# M5921A.net
KiCad netlist of a schematic drawn in EAGLE
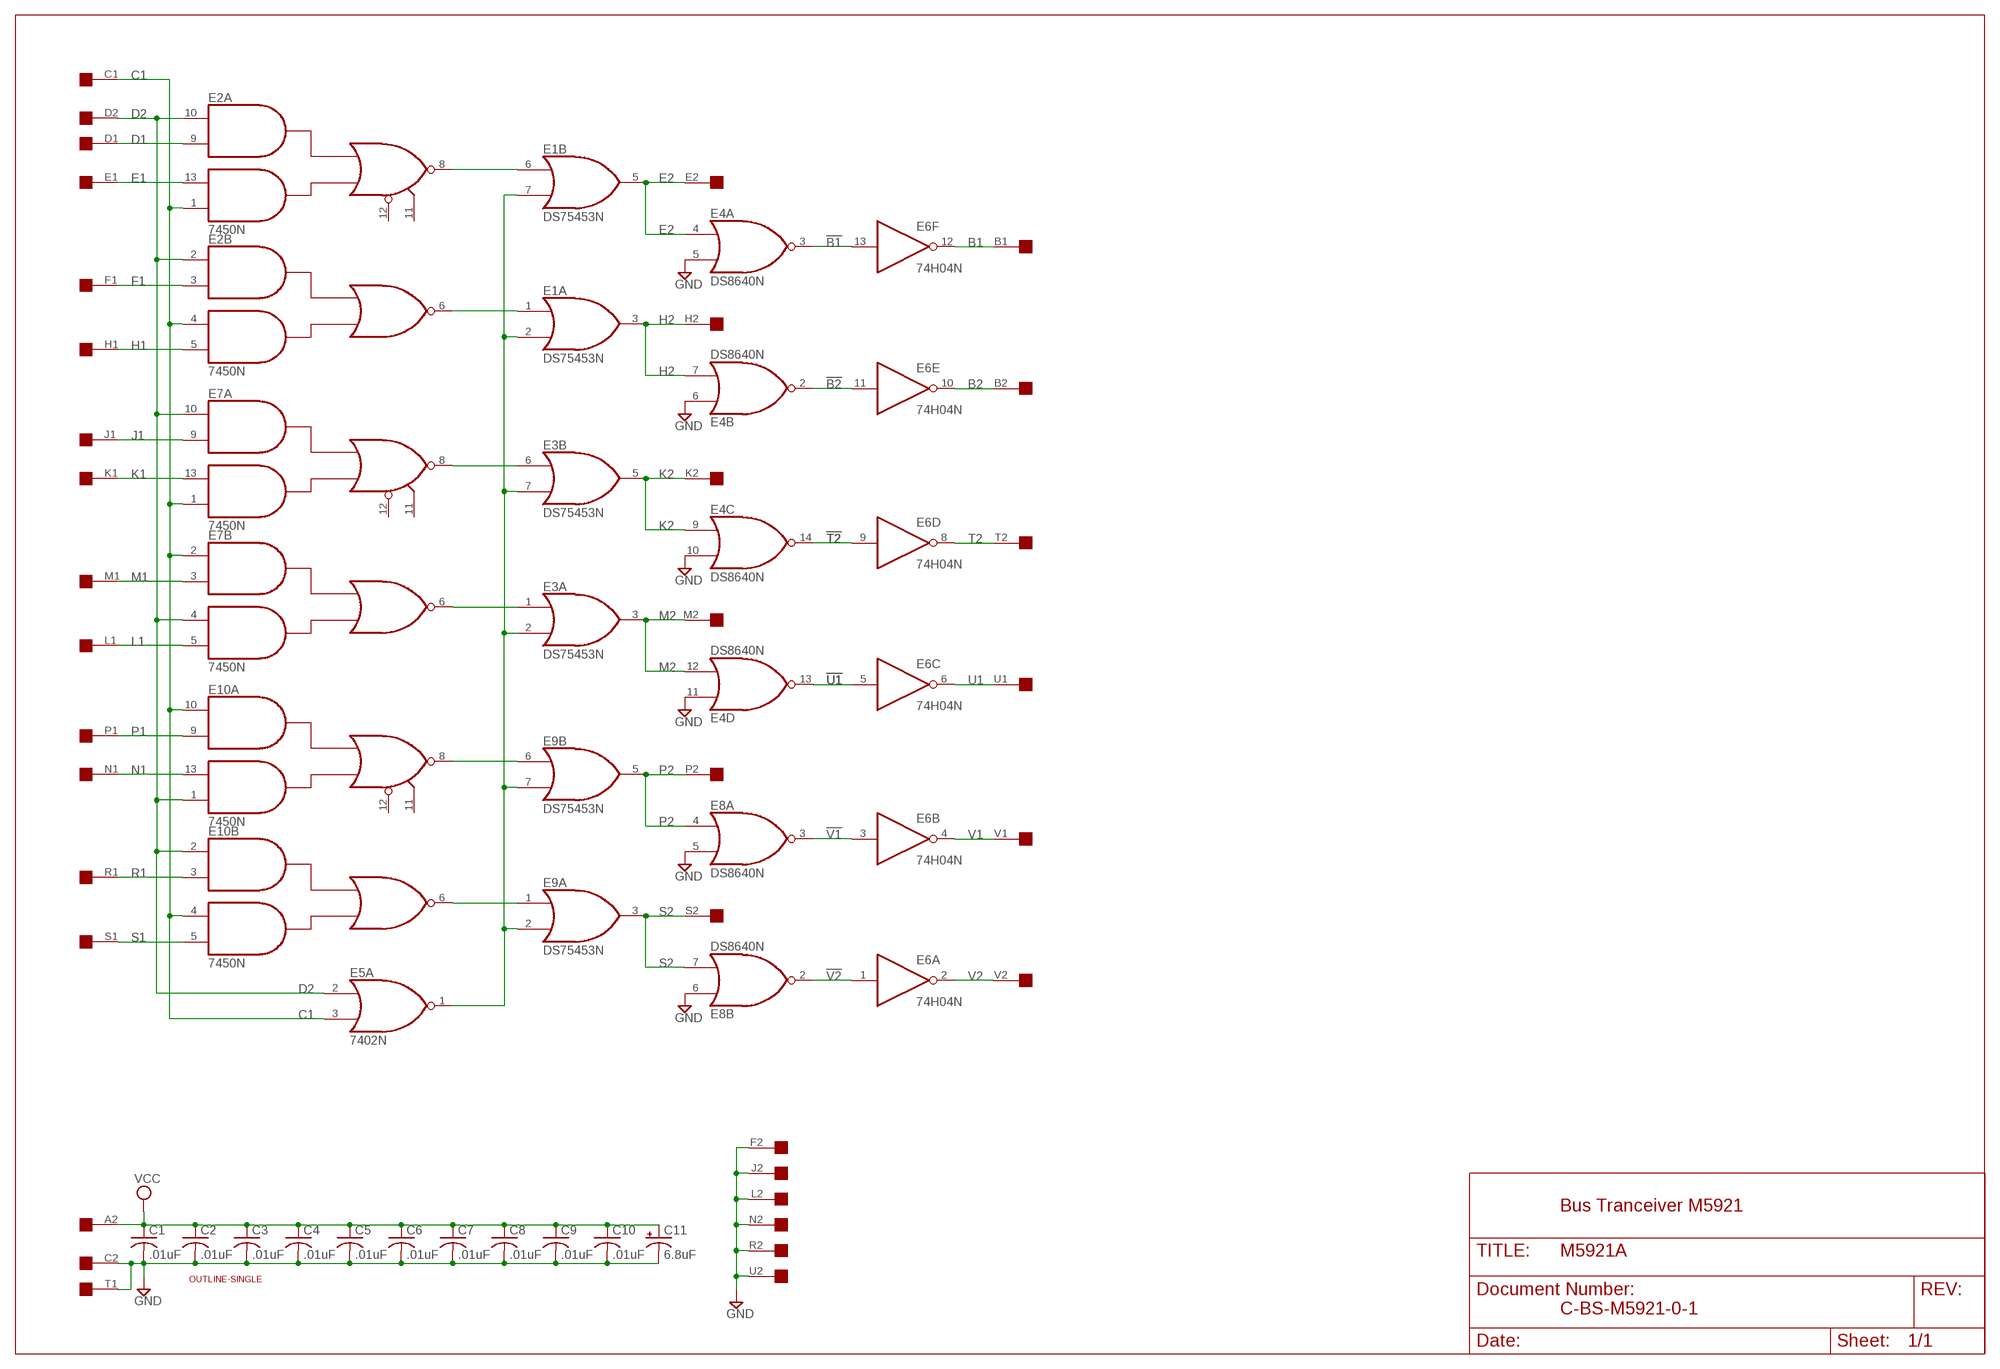
[diagram p0: schematic, sheet 1]

(export (version "E")
  (design (tool "Eeschema 10.0.6"))
  (components
    (comp (ref "C1")
      (value ".01uF")
      (footprint "eagle-import:C063-025X075")
      (libsource (lib "eagle-import") (part "C-US"))
    )
    (comp (ref "C2")
      (value ".01uF")
      (footprint "eagle-import:C063-025X075")
      (libsource (lib "eagle-import") (part "C-US"))
    )
    (comp (ref "C3")
      (value ".01uF")
      (footprint "eagle-import:C063-025X075")
      (libsource (lib "eagle-import") (part "C-US"))
    )
    (comp (ref "C4")
      (value ".01uF")
      (footprint "eagle-import:C063-025X075")
      (libsource (lib "eagle-import") (part "C-US"))
    )
    (comp (ref "C5")
      (value ".01uF")
      (footprint "eagle-import:C063-025X075")
      (libsource (lib "eagle-import") (part "C-US"))
    )
    (comp (ref "C6")
      (value ".01uF")
      (footprint "eagle-import:C063-025X075")
      (libsource (lib "eagle-import") (part "C-US"))
    )
    (comp (ref "C7")
      (value ".01uF")
      (footprint "eagle-import:C063-025X075")
      (libsource (lib "eagle-import") (part "C-US"))
    )
    (comp (ref "C8")
      (value ".01uF")
      (footprint "eagle-import:C063-025X075")
      (libsource (lib "eagle-import") (part "C-US"))
    )
    (comp (ref "C9")
      (value ".01uF")
      (footprint "eagle-import:C063-025X075")
      (libsource (lib "eagle-import") (part "C-US"))
    )
    (comp (ref "C10")
      (value ".01uF")
      (footprint "eagle-import:C063-025X075")
      (libsource (lib "eagle-import") (part "C-US"))
    )
    (comp (ref "C11")
      (value "6.8uF")
      (footprint "eagle-import:E15-5")
      (libsource (lib "eagle-import") (part "CPOL-USE15-5AXIAL"))
    )
    (comp (ref "E1")
      (value "DS75453N")
      (footprint "eagle-import:DIL08")
      (libsource (lib "eagle-import") (part "DS75453N"))
    )
    (comp (ref "E2")
      (value "7450N")
      (footprint "eagle-import:DIL14")
      (libsource (lib "eagle-import") (part "7450N"))
    )
    (comp (ref "E3")
      (value "DS75453N")
      (footprint "eagle-import:DIL08")
      (libsource (lib "eagle-import") (part "DS75453N"))
    )
    (comp (ref "E4")
      (value "DS8640N")
      (footprint "eagle-import:DIL14")
      (libsource (lib "eagle-import") (part "DS8640N"))
    )
    (comp (ref "E5")
      (value "7402N")
      (footprint "eagle-import:DIL14")
      (libsource (lib "eagle-import") (part "7402N"))
    )
    (comp (ref "E6")
      (value "74H04N")
      (footprint "eagle-import:DIL14")
      (libsource (lib "eagle-import") (part "7404NS"))
    )
    (comp (ref "E7")
      (value "7450N")
      (footprint "eagle-import:DIL14")
      (libsource (lib "eagle-import") (part "7450N"))
    )
    (comp (ref "E8")
      (value "DS8640N")
      (footprint "eagle-import:DIL14")
      (libsource (lib "eagle-import") (part "DS8640N"))
    )
    (comp (ref "E9")
      (value "DS75453N")
      (footprint "eagle-import:DIL08")
      (libsource (lib "eagle-import") (part "DS75453N"))
    )
    (comp (ref "E10")
      (value "7450N")
      (footprint "eagle-import:DIL14")
      (libsource (lib "eagle-import") (part "7450N"))
    )
    (comp (ref "U$1")
      (value "OUTLINE-SINGLE")
      (footprint "eagle-import:SINGLE")
      (libsource (lib "eagle-import") (part "OUTLINE-SINGLE"))
    )
    (comp (ref "U$2")
      (value "edge")
      (footprint "eagle-import:EDGE-CON2")
      (libsource (lib "eagle-import") (part "SINGLE"))
    )
  )
  (nets
    (net (code "1") (name "/B1") (class "Default")
      (node (ref "E6") (pin "12") (pinfunction "O_12") (pintype "output"))
      (node (ref "U$2") (pin "B1") (pinfunction "1_B1") (pintype "bidirectional"))
    )
    (net (code "2") (name "/B2") (class "Default")
      (node (ref "E6") (pin "10") (pinfunction "O_10") (pintype "output"))
      (node (ref "U$2") (pin "B2") (pinfunction "1_B2") (pintype "bidirectional"))
    )
    (net (code "3") (name "/C1") (class "Default")
      (node (ref "E10") (pin "10") (pinfunction "I1_10") (pintype "input"))
      (node (ref "E10") (pin "4") (pinfunction "I3_4") (pintype "input"))
      (node (ref "E2") (pin "1") (pinfunction "I4_1") (pintype "input"))
      (node (ref "E2") (pin "4") (pinfunction "I3_4") (pintype "input"))
      (node (ref "E5") (pin "3") (pinfunction "I1_3") (pintype "input"))
      (node (ref "E7") (pin "1") (pinfunction "I4_1") (pintype "input"))
      (node (ref "E7") (pin "2") (pinfunction "I1_2") (pintype "input"))
      (node (ref "U$2") (pin "C1") (pinfunction "1_C1") (pintype "bidirectional"))
    )
    (net (code "4") (name "/D1") (class "Default")
      (node (ref "E2") (pin "9") (pinfunction "I2_9") (pintype "input"))
      (node (ref "U$2") (pin "D1") (pinfunction "1_D1") (pintype "bidirectional"))
    )
    (net (code "5") (name "/D2") (class "Default")
      (node (ref "E10") (pin "1") (pinfunction "I4_1") (pintype "input"))
      (node (ref "E10") (pin "2") (pinfunction "I1_2") (pintype "input"))
      (node (ref "E2") (pin "10") (pinfunction "I1_10") (pintype "input"))
      (node (ref "E2") (pin "2") (pinfunction "I1_2") (pintype "input"))
      (node (ref "E5") (pin "2") (pinfunction "I0_2") (pintype "input"))
      (node (ref "E7") (pin "10") (pinfunction "I1_10") (pintype "input"))
      (node (ref "E7") (pin "4") (pinfunction "I3_4") (pintype "input"))
      (node (ref "U$2") (pin "D2") (pinfunction "1_D2") (pintype "bidirectional"))
    )
    (net (code "6") (name "/E1") (class "Default")
      (node (ref "E2") (pin "13") (pinfunction "I3_13") (pintype "input"))
      (node (ref "U$2") (pin "E1") (pinfunction "1_E1") (pintype "bidirectional"))
    )
    (net (code "7") (name "/E2") (class "Default")
      (node (ref "E1") (pin "5") (pinfunction "O_5") (pintype "open_collector"))
      (node (ref "E4") (pin "4") (pinfunction "I0_4") (pintype "input"))
      (node (ref "U$2") (pin "E2") (pinfunction "1_E2") (pintype "bidirectional"))
    )
    (net (code "8") (name "/F1") (class "Default")
      (node (ref "E2") (pin "3") (pinfunction "I2_3") (pintype "input"))
      (node (ref "U$2") (pin "F1") (pinfunction "1_F1") (pintype "bidirectional"))
    )
    (net (code "9") (name "/H1") (class "Default")
      (node (ref "E2") (pin "5") (pinfunction "I4_5") (pintype "input"))
      (node (ref "U$2") (pin "H1") (pinfunction "1_H1") (pintype "bidirectional"))
    )
    (net (code "10") (name "/H2") (class "Default")
      (node (ref "E1") (pin "3") (pinfunction "O_3") (pintype "open_collector"))
      (node (ref "E4") (pin "7") (pinfunction "I1_7") (pintype "input"))
      (node (ref "U$2") (pin "H2") (pinfunction "1_H2") (pintype "bidirectional"))
    )
    (net (code "11") (name "/J1") (class "Default")
      (node (ref "E7") (pin "9") (pinfunction "I2_9") (pintype "input"))
      (node (ref "U$2") (pin "J1") (pinfunction "1_J1") (pintype "bidirectional"))
    )
    (net (code "12") (name "/K1") (class "Default")
      (node (ref "E7") (pin "13") (pinfunction "I3_13") (pintype "input"))
      (node (ref "U$2") (pin "K1") (pinfunction "1_K1") (pintype "bidirectional"))
    )
    (net (code "13") (name "/K2") (class "Default")
      (node (ref "E3") (pin "5") (pinfunction "O_5") (pintype "open_collector"))
      (node (ref "E4") (pin "9") (pinfunction "I0_9") (pintype "input"))
      (node (ref "U$2") (pin "K2") (pinfunction "1_K2") (pintype "bidirectional"))
    )
    (net (code "14") (name "/L1") (class "Default")
      (node (ref "E7") (pin "5") (pinfunction "I4_5") (pintype "input"))
      (node (ref "U$2") (pin "L1") (pinfunction "1_L1") (pintype "bidirectional"))
    )
    (net (code "15") (name "/M1") (class "Default")
      (node (ref "E7") (pin "3") (pinfunction "I2_3") (pintype "input"))
      (node (ref "U$2") (pin "M1") (pinfunction "1_M1") (pintype "bidirectional"))
    )
    (net (code "16") (name "/M2") (class "Default")
      (node (ref "E3") (pin "3") (pinfunction "O_3") (pintype "open_collector"))
      (node (ref "E4") (pin "12") (pinfunction "I1_12") (pintype "input"))
      (node (ref "U$2") (pin "M2") (pinfunction "1_M2") (pintype "bidirectional"))
    )
    (net (code "17") (name "/N1") (class "Default")
      (node (ref "E10") (pin "13") (pinfunction "I3_13") (pintype "input"))
      (node (ref "U$2") (pin "N1") (pinfunction "1_N1") (pintype "bidirectional"))
    )
    (net (code "18") (name "/P1") (class "Default")
      (node (ref "E10") (pin "9") (pinfunction "I2_9") (pintype "input"))
      (node (ref "U$2") (pin "P1") (pinfunction "1_P1") (pintype "bidirectional"))
    )
    (net (code "19") (name "/P2") (class "Default")
      (node (ref "E8") (pin "4") (pinfunction "I0_4") (pintype "input"))
      (node (ref "E9") (pin "5") (pinfunction "O_5") (pintype "open_collector"))
      (node (ref "U$2") (pin "P2") (pinfunction "1_P2") (pintype "bidirectional"))
    )
    (net (code "20") (name "/R1") (class "Default")
      (node (ref "E10") (pin "3") (pinfunction "I2_3") (pintype "input"))
      (node (ref "U$2") (pin "R1") (pinfunction "1_R1") (pintype "bidirectional"))
    )
    (net (code "21") (name "/S1") (class "Default")
      (node (ref "E10") (pin "5") (pinfunction "I4_5") (pintype "input"))
      (node (ref "U$2") (pin "S1") (pinfunction "1_S1") (pintype "bidirectional"))
    )
    (net (code "22") (name "/S2") (class "Default")
      (node (ref "E8") (pin "7") (pinfunction "I1_7") (pintype "input"))
      (node (ref "E9") (pin "3") (pinfunction "O_3") (pintype "open_collector"))
      (node (ref "U$2") (pin "S2") (pinfunction "1_S2") (pintype "bidirectional"))
    )
    (net (code "23") (name "/T2") (class "Default")
      (node (ref "E6") (pin "8") (pinfunction "O_8") (pintype "output"))
      (node (ref "U$2") (pin "T2") (pinfunction "1_T2") (pintype "bidirectional"))
    )
    (net (code "24") (name "/U1") (class "Default")
      (node (ref "E6") (pin "6") (pinfunction "O_6") (pintype "output"))
      (node (ref "U$2") (pin "U1") (pinfunction "1_U1") (pintype "bidirectional"))
    )
    (net (code "25") (name "/V1") (class "Default")
      (node (ref "E6") (pin "4") (pinfunction "O_4") (pintype "output"))
      (node (ref "U$2") (pin "V1") (pinfunction "1_V1") (pintype "bidirectional"))
    )
    (net (code "26") (name "/V2") (class "Default")
      (node (ref "E6") (pin "2") (pinfunction "O_2") (pintype "output"))
      (node (ref "U$2") (pin "V2") (pinfunction "1_V2") (pintype "bidirectional"))
    )
    (net (code "27") (name "/~{B1}") (class "Default")
      (node (ref "E4") (pin "3") (pinfunction "O_3") (pintype "output"))
      (node (ref "E6") (pin "13") (pinfunction "I_13") (pintype "input"))
    )
    (net (code "28") (name "/~{B2}") (class "Default")
      (node (ref "E4") (pin "2") (pinfunction "O_2") (pintype "output"))
      (node (ref "E6") (pin "11") (pinfunction "I_11") (pintype "input"))
    )
    (net (code "29") (name "/~{T2}") (class "Default")
      (node (ref "E4") (pin "14") (pinfunction "O_14") (pintype "output"))
      (node (ref "E6") (pin "9") (pinfunction "I_9") (pintype "input"))
    )
    (net (code "30") (name "/~{U1}") (class "Default")
      (node (ref "E4") (pin "13") (pinfunction "O_13") (pintype "output"))
      (node (ref "E6") (pin "5") (pinfunction "I_5") (pintype "input"))
    )
    (net (code "31") (name "/~{V1}") (class "Default")
      (node (ref "E6") (pin "3") (pinfunction "I_3") (pintype "input"))
      (node (ref "E8") (pin "3") (pinfunction "O_3") (pintype "output"))
    )
    (net (code "32") (name "/~{V2}") (class "Default")
      (node (ref "E6") (pin "1") (pinfunction "I_1") (pintype "input"))
      (node (ref "E8") (pin "2") (pinfunction "O_2") (pintype "output"))
    )
    (net (code "33") (name "GND") (class "Default")
      (node (ref "C1") (pin "2") (pinfunction "2_2") (pintype "passive"))
      (node (ref "C10") (pin "2") (pinfunction "2_2") (pintype "passive"))
      (node (ref "C11") (pin "-") (pinfunction "-_-") (pintype "passive"))
      (node (ref "C2") (pin "2") (pinfunction "2_2") (pintype "passive"))
      (node (ref "C3") (pin "2") (pinfunction "2_2") (pintype "passive"))
      (node (ref "C4") (pin "2") (pinfunction "2_2") (pintype "passive"))
      (node (ref "C5") (pin "2") (pinfunction "2_2") (pintype "passive"))
      (node (ref "C6") (pin "2") (pinfunction "2_2") (pintype "passive"))
      (node (ref "C7") (pin "2") (pinfunction "2_2") (pintype "passive"))
      (node (ref "C8") (pin "2") (pinfunction "2_2") (pintype "passive"))
      (node (ref "C9") (pin "2") (pinfunction "2_2") (pintype "passive"))
      (node (ref "E4") (pin "10") (pinfunction "I1_10") (pintype "input"))
      (node (ref "E4") (pin "11") (pinfunction "I0_11") (pintype "input"))
      (node (ref "E4") (pin "5") (pinfunction "I1_5") (pintype "input"))
      (node (ref "E4") (pin "6") (pinfunction "I0_6") (pintype "input"))
      (node (ref "E8") (pin "5") (pinfunction "I1_5") (pintype "input"))
      (node (ref "E8") (pin "6") (pinfunction "I0_6") (pintype "input"))
      (node (ref "U$2") (pin "C2") (pinfunction "1_C2") (pintype "bidirectional"))
      (node (ref "U$2") (pin "F2") (pinfunction "1_F2") (pintype "bidirectional"))
      (node (ref "U$2") (pin "J2") (pinfunction "1_J2") (pintype "bidirectional"))
      (node (ref "U$2") (pin "L2") (pinfunction "1_L2") (pintype "bidirectional"))
      (node (ref "U$2") (pin "N2") (pinfunction "1_N2") (pintype "bidirectional"))
      (node (ref "U$2") (pin "R2") (pinfunction "1_R2") (pintype "bidirectional"))
      (node (ref "U$2") (pin "T1") (pinfunction "1_T1") (pintype "bidirectional"))
      (node (ref "U$2") (pin "U2") (pinfunction "1_U2") (pintype "bidirectional"))
    )
    (net (code "34") (name "Net-(E1A-I0)") (class "Default")
      (node (ref "E1") (pin "1") (pinfunction "I0_1") (pintype "input"))
      (node (ref "E2") (pin "6") (pinfunction "O_6") (pintype "output"))
    )
    (net (code "35") (name "Net-(E1A-I1)") (class "Default")
      (node (ref "E1") (pin "2") (pinfunction "I1_2") (pintype "input"))
      (node (ref "E1") (pin "7") (pinfunction "I1_7") (pintype "input"))
      (node (ref "E3") (pin "2") (pinfunction "I1_2") (pintype "input"))
      (node (ref "E3") (pin "7") (pinfunction "I1_7") (pintype "input"))
      (node (ref "E5") (pin "1") (pinfunction "O_1") (pintype "output"))
      (node (ref "E9") (pin "2") (pinfunction "I1_2") (pintype "input"))
      (node (ref "E9") (pin "7") (pinfunction "I1_7") (pintype "input"))
    )
    (net (code "36") (name "Net-(E1B-I0)") (class "Default")
      (node (ref "E1") (pin "6") (pinfunction "I0_6") (pintype "input"))
      (node (ref "E2") (pin "8") (pinfunction "O_8") (pintype "output"))
    )
    (net (code "37") (name "Net-(E3A-I0)") (class "Default")
      (node (ref "E3") (pin "1") (pinfunction "I0_1") (pintype "input"))
      (node (ref "E7") (pin "6") (pinfunction "O_6") (pintype "output"))
    )
    (net (code "38") (name "Net-(E3B-I0)") (class "Default")
      (node (ref "E3") (pin "6") (pinfunction "I0_6") (pintype "input"))
      (node (ref "E7") (pin "8") (pinfunction "O_8") (pintype "output"))
    )
    (net (code "39") (name "Net-(E10A-O)") (class "Default")
      (node (ref "E10") (pin "8") (pinfunction "O_8") (pintype "output"))
      (node (ref "E9") (pin "6") (pinfunction "I0_6") (pintype "input"))
    )
    (net (code "40") (name "Net-(E10B-O)") (class "Default")
      (node (ref "E10") (pin "6") (pinfunction "O_6") (pintype "output"))
      (node (ref "E9") (pin "1") (pinfunction "I0_1") (pintype "input"))
    )
    (net (code "41") (name "VCC") (class "Default")
      (node (ref "C1") (pin "1") (pinfunction "1_1") (pintype "passive"))
      (node (ref "C10") (pin "1") (pinfunction "1_1") (pintype "passive"))
      (node (ref "C11") (pin "+") (pinfunction "+_+") (pintype "passive"))
      (node (ref "C2") (pin "1") (pinfunction "1_1") (pintype "passive"))
      (node (ref "C3") (pin "1") (pinfunction "1_1") (pintype "passive"))
      (node (ref "C4") (pin "1") (pinfunction "1_1") (pintype "passive"))
      (node (ref "C5") (pin "1") (pinfunction "1_1") (pintype "passive"))
      (node (ref "C6") (pin "1") (pinfunction "1_1") (pintype "passive"))
      (node (ref "C7") (pin "1") (pinfunction "1_1") (pintype "passive"))
      (node (ref "C8") (pin "1") (pinfunction "1_1") (pintype "passive"))
      (node (ref "C9") (pin "1") (pinfunction "1_1") (pintype "passive"))
      (node (ref "U$2") (pin "A2") (pinfunction "1_A2") (pintype "bidirectional"))
    )
    (net (code "42") (name "unconnected-(E2A-I5-Pad12)") (class "Default")
      (node (ref "E2") (pin "12") (pinfunction "I5_12") (pintype "passive"))
    )
    (net (code "43") (name "unconnected-(E2A-I6-Pad11)") (class "Default")
      (node (ref "E2") (pin "11") (pinfunction "I6_11") (pintype "passive"))
    )
    (net (code "44") (name "unconnected-(E7A-I5-Pad12)") (class "Default")
      (node (ref "E7") (pin "12") (pinfunction "I5_12") (pintype "passive"))
    )
    (net (code "45") (name "unconnected-(E7A-I6-Pad11)") (class "Default")
      (node (ref "E7") (pin "11") (pinfunction "I6_11") (pintype "passive"))
    )
    (net (code "46") (name "unconnected-(E10A-I5-Pad12)") (class "Default")
      (node (ref "E10") (pin "12") (pinfunction "I5_12") (pintype "passive"))
    )
    (net (code "47") (name "unconnected-(E10A-I6-Pad11)") (class "Default")
      (node (ref "E10") (pin "11") (pinfunction "I6_11") (pintype "passive"))
    )
  )
)
